# SpO2.net
KiCad netlist of a schematic drawn in EAGLE
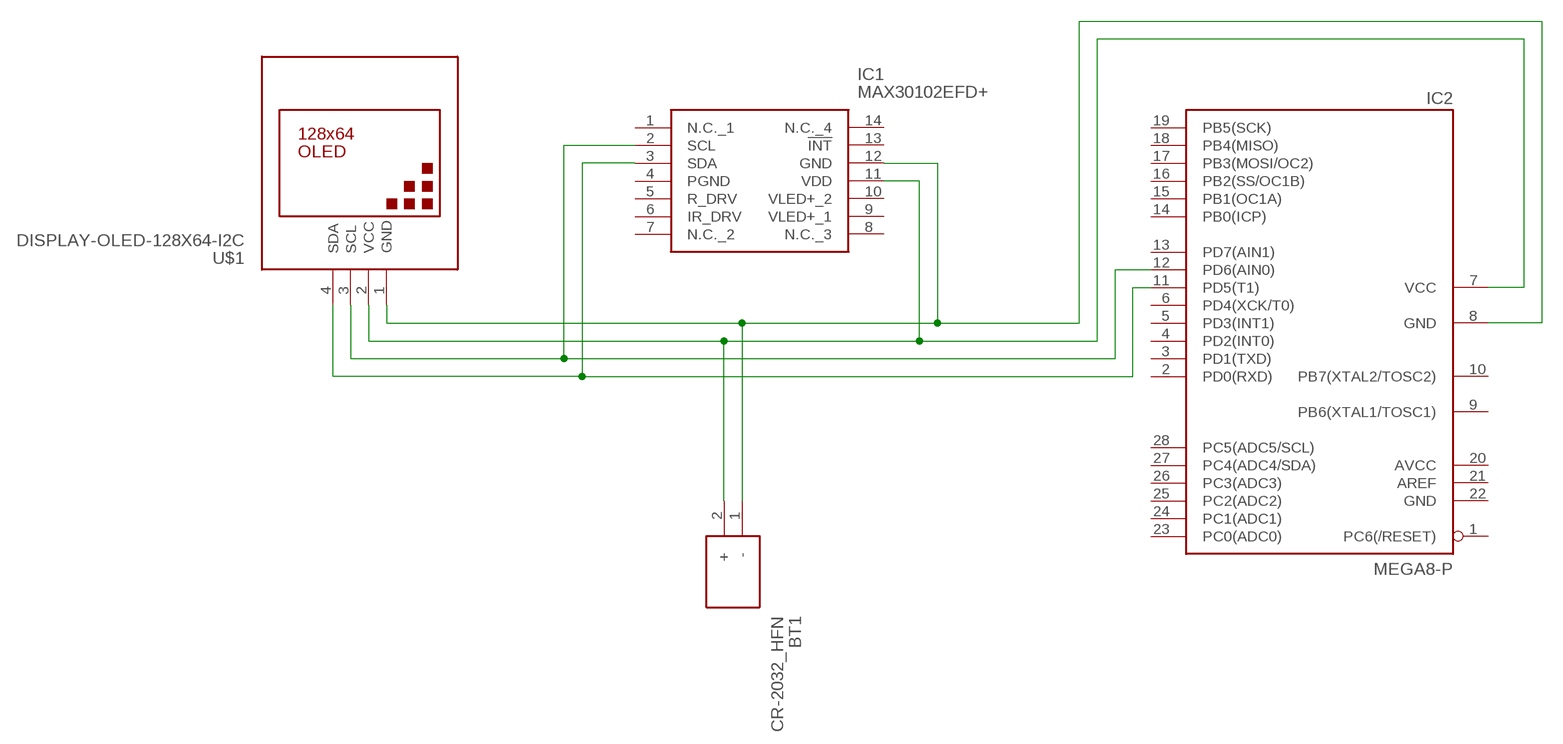
[diagram p0: schematic, sheet 1]

(export (version "E")
  (design (tool "Eeschema 10.0.6"))
  (components
    (comp (ref "BT1")
      (value "CR-2032_HFN")
      (footprint "eagle-import:CR-2032HFN")
      (fields
        (field (name "ARROW_PART_NUMBER") "CR-2032/HFN")
        (field (name "MOUSER_PART_NUMBER") "658-CR-2032/HFN")
      )
      (libsource (lib "eagle-import") (part "CR-2032_HFN"))
    )
    (comp (ref "IC1")
      (value "MAX30102EFD+")
      (footprint "eagle-import:14-LEAD-OESIP")
      (fields (field (name "MOUSER_PART_NUMBER") "700-MAX30102EFD+"))
      (libsource (lib "eagle-import") (part "MAX30102EFD+"))
    )
    (comp (ref "IC2")
      (value "MEGA8-P")
      (footprint "eagle-import:DIL28-3")
      (libsource (lib "eagle-import") (part "MEGA8-P"))
    )
    (comp (ref "U$1")
      (value "DISPLAY-OLED-128X64-I2C")
      (footprint "eagle-import:DISPLAY-OLED-128X64-I2C")
      (libsource (lib "eagle-import") (part "DISPLAY-OLED-128X64-I2C"))
    )
  )
  (nets
    (net (code "1") (name "/AVCC") (class "Default")
      (node (ref "IC2") (pin "20") (pinfunction "AVCC_20") (pintype "power_in"))
    )
    (net (code "2") (name "/GND") (class "Default")
      (node (ref "IC2") (pin "22") (pinfunction "GND_22") (pintype "power_in"))
    )
    (net (code "3") (name "Net-(BT1-+)") (class "Default")
      (node (ref "BT1") (pin "2") (pinfunction "+_2") (pintype "bidirectional"))
      (node (ref "IC1") (pin "11") (pinfunction "VDD_11") (pintype "bidirectional"))
      (node (ref "IC2") (pin "7") (pinfunction "VCC_7") (pintype "power_in"))
      (node (ref "U$1") (pin "2") (pinfunction "VCC_2") (pintype "power_in"))
    )
    (net (code "4") (name "Net-(BT1--)") (class "Default")
      (node (ref "BT1") (pin "1") (pinfunction "-_1") (pintype "bidirectional"))
      (node (ref "IC1") (pin "12") (pinfunction "GND_12") (pintype "bidirectional"))
      (node (ref "IC2") (pin "8") (pinfunction "GND_8") (pintype "power_in"))
      (node (ref "U$1") (pin "1") (pinfunction "GND_1") (pintype "power_in"))
    )
    (net (code "5") (name "Net-(IC1-SCL)") (class "Default")
      (node (ref "IC1") (pin "2") (pinfunction "SCL_2") (pintype "bidirectional"))
      (node (ref "IC2") (pin "12") (pinfunction "PD6(AIN0)_12") (pintype "bidirectional"))
      (node (ref "U$1") (pin "3") (pinfunction "SCL_3") (pintype "bidirectional"))
    )
    (net (code "6") (name "Net-(IC1-SDA)") (class "Default")
      (node (ref "IC1") (pin "3") (pinfunction "SDA_3") (pintype "bidirectional"))
      (node (ref "IC2") (pin "11") (pinfunction "PD5(T1)_11") (pintype "bidirectional"))
      (node (ref "U$1") (pin "4") (pinfunction "SDA_4") (pintype "bidirectional"))
    )
    (net (code "7") (name "unconnected-(IC1-IR_DRV-Pad6)") (class "Default")
      (node (ref "IC1") (pin "6") (pinfunction "IR_DRV_6") (pintype "bidirectional"))
    )
    (net (code "8") (name "unconnected-(IC1-N.C._1-Pad1)") (class "Default")
      (node (ref "IC1") (pin "1") (pinfunction "N.C._1_1") (pintype "bidirectional"))
    )
    (net (code "9") (name "unconnected-(IC1-N.C._2-Pad7)") (class "Default")
      (node (ref "IC1") (pin "7") (pinfunction "N.C._2_7") (pintype "bidirectional"))
    )
    (net (code "10") (name "unconnected-(IC1-N.C._3-Pad8)") (class "Default")
      (node (ref "IC1") (pin "8") (pinfunction "N.C._3_8") (pintype "bidirectional"))
    )
    (net (code "11") (name "unconnected-(IC1-N.C._4-Pad14)") (class "Default")
      (node (ref "IC1") (pin "14") (pinfunction "N.C._4_14") (pintype "bidirectional"))
    )
    (net (code "12") (name "unconnected-(IC1-PGND-Pad4)") (class "Default")
      (node (ref "IC1") (pin "4") (pinfunction "PGND_4") (pintype "bidirectional"))
    )
    (net (code "13") (name "unconnected-(IC1-R_DRV-Pad5)") (class "Default")
      (node (ref "IC1") (pin "5") (pinfunction "R_DRV_5") (pintype "bidirectional"))
    )
    (net (code "14") (name "unconnected-(IC1-VLED+_1-Pad9)") (class "Default")
      (node (ref "IC1") (pin "9") (pinfunction "VLED+_1_9") (pintype "bidirectional"))
    )
    (net (code "15") (name "unconnected-(IC1-VLED+_2-Pad10)") (class "Default")
      (node (ref "IC1") (pin "10") (pinfunction "VLED+_2_10") (pintype "bidirectional"))
    )
    (net (code "16") (name "unconnected-(IC1-~{INT}-Pad13)") (class "Default")
      (node (ref "IC1") (pin "13") (pinfunction "~{INT}_13") (pintype "bidirectional"))
    )
    (net (code "17") (name "unconnected-(IC2-AREF-Pad21)") (class "Default")
      (node (ref "IC2") (pin "21") (pinfunction "AREF_21") (pintype "passive"))
    )
    (net (code "18") (name "unconnected-(IC2-PB0(ICP)-Pad14)") (class "Default")
      (node (ref "IC2") (pin "14") (pinfunction "PB0(ICP)_14") (pintype "bidirectional"))
    )
    (net (code "19") (name "unconnected-(IC2-PB1(OC1A)-Pad15)") (class "Default")
      (node (ref "IC2") (pin "15") (pinfunction "PB1(OC1A)_15") (pintype "bidirectional"))
    )
    (net (code "20") (name "unconnected-(IC2-PB2(SS{slash}OC1B)-Pad16)") (class "Default")
      (node (ref "IC2") (pin "16") (pinfunction "PB2(SS/OC1B)_16") (pintype "bidirectional"))
    )
    (net (code "21") (name "unconnected-(IC2-PB3(MOSI{slash}OC2)-Pad17)") (class "Default")
      (node (ref "IC2") (pin "17") (pinfunction "PB3(MOSI/OC2)_17") (pintype "bidirectional"))
    )
    (net (code "22") (name "unconnected-(IC2-PB4(MISO)-Pad18)") (class "Default")
      (node (ref "IC2") (pin "18") (pinfunction "PB4(MISO)_18") (pintype "bidirectional"))
    )
    (net (code "23") (name "unconnected-(IC2-PB5(SCK)-Pad19)") (class "Default")
      (node (ref "IC2") (pin "19") (pinfunction "PB5(SCK)_19") (pintype "bidirectional"))
    )
    (net (code "24") (name "unconnected-(IC2-PB6(XTAL1{slash}TOSC1)-Pad9)") (class "Default")
      (node (ref "IC2") (pin "9") (pinfunction "PB6(XTAL1/TOSC1)_9") (pintype "bidirectional"))
    )
    (net (code "25") (name "unconnected-(IC2-PB7(XTAL2{slash}TOSC2)-Pad10)") (class "Default")
      (node (ref "IC2") (pin "10") (pinfunction "PB7(XTAL2/TOSC2)_10") (pintype "bidirectional"))
    )
    (net (code "26") (name "unconnected-(IC2-PC0(ADC0)-Pad23)") (class "Default")
      (node (ref "IC2") (pin "23") (pinfunction "PC0(ADC0)_23") (pintype "bidirectional"))
    )
    (net (code "27") (name "unconnected-(IC2-PC1(ADC1)-Pad24)") (class "Default")
      (node (ref "IC2") (pin "24") (pinfunction "PC1(ADC1)_24") (pintype "bidirectional"))
    )
    (net (code "28") (name "unconnected-(IC2-PC2(ADC2)-Pad25)") (class "Default")
      (node (ref "IC2") (pin "25") (pinfunction "PC2(ADC2)_25") (pintype "bidirectional"))
    )
    (net (code "29") (name "unconnected-(IC2-PC3(ADC3)-Pad26)") (class "Default")
      (node (ref "IC2") (pin "26") (pinfunction "PC3(ADC3)_26") (pintype "bidirectional"))
    )
    (net (code "30") (name "unconnected-(IC2-PC4(ADC4{slash}SDA)-Pad27)") (class "Default")
      (node (ref "IC2") (pin "27") (pinfunction "PC4(ADC4/SDA)_27") (pintype "bidirectional"))
    )
    (net (code "31") (name "unconnected-(IC2-PC5(ADC5{slash}SCL)-Pad28)") (class "Default")
      (node (ref "IC2") (pin "28") (pinfunction "PC5(ADC5/SCL)_28") (pintype "bidirectional"))
    )
    (net (code "32") (name "unconnected-(IC2-PC6({slash}RESET)-Pad1)") (class "Default")
      (node (ref "IC2") (pin "1") (pinfunction "PC6(/RESET)_1") (pintype "bidirectional"))
    )
    (net (code "33") (name "unconnected-(IC2-PD0(RXD)-Pad2)") (class "Default")
      (node (ref "IC2") (pin "2") (pinfunction "PD0(RXD)_2") (pintype "bidirectional"))
    )
    (net (code "34") (name "unconnected-(IC2-PD1(TXD)-Pad3)") (class "Default")
      (node (ref "IC2") (pin "3") (pinfunction "PD1(TXD)_3") (pintype "bidirectional"))
    )
    (net (code "35") (name "unconnected-(IC2-PD2(INT0)-Pad4)") (class "Default")
      (node (ref "IC2") (pin "4") (pinfunction "PD2(INT0)_4") (pintype "bidirectional"))
    )
    (net (code "36") (name "unconnected-(IC2-PD3(INT1)-Pad5)") (class "Default")
      (node (ref "IC2") (pin "5") (pinfunction "PD3(INT1)_5") (pintype "bidirectional"))
    )
    (net (code "37") (name "unconnected-(IC2-PD4(XCK{slash}T0)-Pad6)") (class "Default")
      (node (ref "IC2") (pin "6") (pinfunction "PD4(XCK/T0)_6") (pintype "bidirectional"))
    )
    (net (code "38") (name "unconnected-(IC2-PD7(AIN1)-Pad13)") (class "Default")
      (node (ref "IC2") (pin "13") (pinfunction "PD7(AIN1)_13") (pintype "bidirectional"))
    )
  )
)
